# Breakout.net
KiCad netlist of a schematic drawn in EAGLE
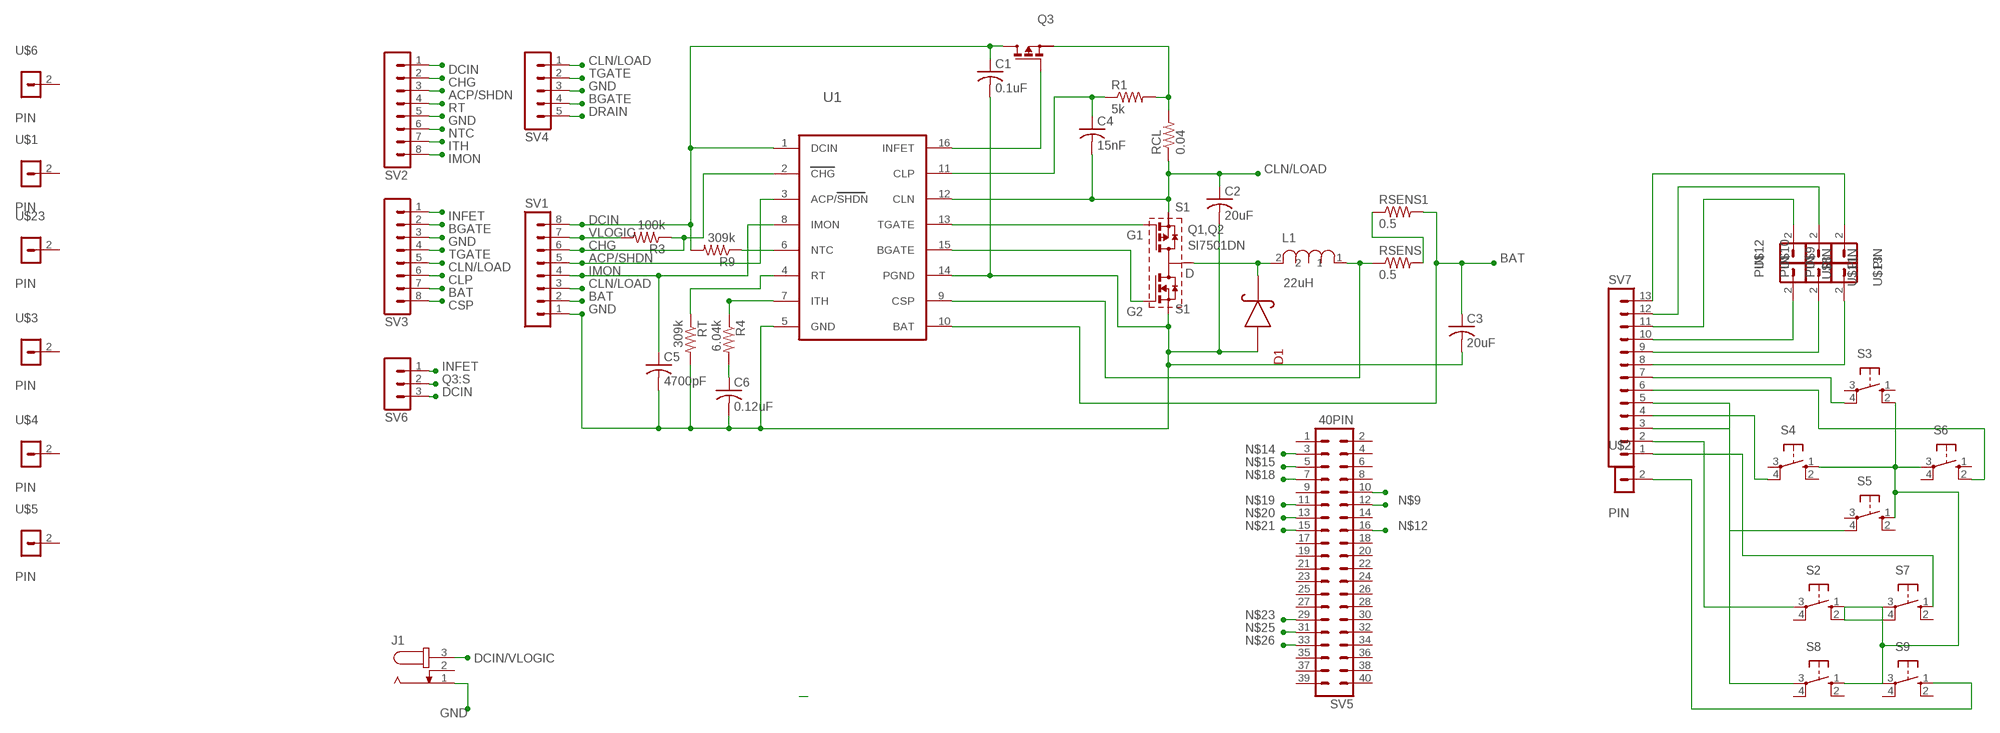
[diagram p0: schematic, sheet 1]

(export (version "E")
  (design (tool "Eeschema 10.0.6"))
  (components
    (comp (ref "C1")
      (value "0.1uF")
      (footprint "eagle-import:C1210")
      (libsource (lib "eagle-import") (part "C-USC1210"))
    )
    (comp (ref "C2")
      (value "20uF")
      (footprint "eagle-import:C1210")
      (libsource (lib "eagle-import") (part "C-USC1210"))
    )
    (comp (ref "C3")
      (value "20uF")
      (footprint "eagle-import:C1210")
      (libsource (lib "eagle-import") (part "C-USC1210"))
    )
    (comp (ref "C4")
      (value "15nF")
      (footprint "eagle-import:C1210")
      (libsource (lib "eagle-import") (part "C-USC1210"))
    )
    (comp (ref "C5")
      (value "4700pF")
      (footprint "eagle-import:C1210")
      (libsource (lib "eagle-import") (part "C-USC1210"))
    )
    (comp (ref "C6")
      (value "0.12uF")
      (footprint "eagle-import:C1210")
      (libsource (lib "eagle-import") (part "C-USC1210"))
    )
    (comp (ref "D1")
      (value "DIODE")
      (footprint "eagle-import:DIODE")
      (libsource (lib "eagle-import") (part "DIODE"))
    )
    (comp (ref "J1")
      (value "JACK-PLUG0")
      (footprint "eagle-import:SPC4077")
      (libsource (lib "eagle-import") (part "JACK-PLUG0"))
    )
    (comp (ref "L1")
      (value "22uH")
      (footprint "eagle-import:POWERINDUCTOR")
      (libsource (lib "eagle-import") (part "SDR1005INDUCTOR"))
    )
    (comp (ref "Q1,Q2")
      (value "SI7501DN")
      (footprint "eagle-import:POWERPAK")
      (libsource (lib "eagle-import") (part "SI7501DN"))
    )
    (comp (ref "Q3")
      (value "MOSFET")
      (footprint "eagle-import:SOT-23")
      (libsource (lib "eagle-import") (part "MOSFET"))
    )
    (comp (ref "R1")
      (value "5k")
      (footprint "eagle-import:R1206")
      (libsource (lib "eagle-import") (part "R-US_R1206"))
    )
    (comp (ref "R3")
      (value "100k")
      (footprint "eagle-import:R1206")
      (libsource (lib "eagle-import") (part "R-US_R1206"))
    )
    (comp (ref "R4")
      (value "6.04k")
      (footprint "eagle-import:R1206")
      (libsource (lib "eagle-import") (part "R-US_R1206"))
    )
    (comp (ref "R9")
      (value "309k")
      (footprint "eagle-import:R1206")
      (libsource (lib "eagle-import") (part "R-US_R1206"))
    )
    (comp (ref "RCL")
      (value "0.04")
      (footprint "eagle-import:R1206")
      (libsource (lib "eagle-import") (part "R-US_R1206"))
    )
    (comp (ref "RSENS")
      (value "0.5")
      (footprint "eagle-import:0612_1632")
      (libsource (lib "eagle-import") (part "0612/1632"))
    )
    (comp (ref "RSENS1")
      (value "0.5")
      (footprint "eagle-import:0612_1632")
      (libsource (lib "eagle-import") (part "0612/1632"))
    )
    (comp (ref "RT")
      (value "309k")
      (footprint "eagle-import:R1206")
      (libsource (lib "eagle-import") (part "R-US_R1206"))
    )
    (comp (ref "S2")
      (value "10-XX")
      (footprint "eagle-import:B3F-10XX")
      (fields (field (name "MPN") "B3F-1000"))
      (libsource (lib "eagle-import") (part "10-XX"))
    )
    (comp (ref "S3")
      (value "10-XX")
      (footprint "eagle-import:B3F-10XX")
      (fields (field (name "MPN") "B3F-1000"))
      (libsource (lib "eagle-import") (part "10-XX"))
    )
    (comp (ref "S4")
      (value "10-XX")
      (footprint "eagle-import:B3F-10XX")
      (fields (field (name "MPN") "B3F-1000"))
      (libsource (lib "eagle-import") (part "10-XX"))
    )
    (comp (ref "S5")
      (value "10-XX")
      (footprint "eagle-import:B3F-10XX")
      (fields (field (name "MPN") "B3F-1000"))
      (libsource (lib "eagle-import") (part "10-XX"))
    )
    (comp (ref "S6")
      (value "10-XX")
      (footprint "eagle-import:B3F-10XX")
      (fields (field (name "MPN") "B3F-1000"))
      (libsource (lib "eagle-import") (part "10-XX"))
    )
    (comp (ref "S7")
      (value "10-XX")
      (footprint "eagle-import:B3F-10XX")
      (fields (field (name "MPN") "B3F-1000"))
      (libsource (lib "eagle-import") (part "10-XX"))
    )
    (comp (ref "S8")
      (value "10-XX")
      (footprint "eagle-import:B3F-10XX")
      (fields (field (name "MPN") "B3F-1000"))
      (libsource (lib "eagle-import") (part "10-XX"))
    )
    (comp (ref "S9")
      (value "10-XX")
      (footprint "eagle-import:B3F-10XX")
      (fields (field (name "MPN") "B3F-1000"))
      (libsource (lib "eagle-import") (part "10-XX"))
    )
    (comp (ref "SV1")
      (value "MA08-1")
      (footprint "eagle-import:MA08-1")
      (libsource (lib "eagle-import") (part "MA08-1"))
    )
    (comp (ref "SV2")
      (value "MA08-1")
      (footprint "eagle-import:MA08-1")
      (libsource (lib "eagle-import") (part "MA08-1"))
    )
    (comp (ref "SV3")
      (value "MA08-1")
      (footprint "eagle-import:MA08-1")
      (libsource (lib "eagle-import") (part "MA08-1"))
    )
    (comp (ref "SV4")
      (value "MA05-1")
      (footprint "eagle-import:MA05-1")
      (libsource (lib "eagle-import") (part "MA05-1"))
    )
    (comp (ref "SV5")
      (value "40PIN")
      (footprint "eagle-import:40PINHEADDER")
      (libsource (lib "eagle-import") (part "40PIN"))
    )
    (comp (ref "SV6")
      (value "MA03-1")
      (footprint "eagle-import:MA03-1")
      (libsource (lib "eagle-import") (part "MA03-1"))
    )
    (comp (ref "SV7")
      (value "MA13-1")
      (footprint "eagle-import:MA13-1")
      (libsource (lib "eagle-import") (part "MA13-1"))
    )
    (comp (ref "U$1")
      (value "PIN")
      (footprint "eagle-import:PIN")
      (libsource (lib "eagle-import") (part "PIN"))
    )
    (comp (ref "U$2")
      (value "PIN")
      (footprint "eagle-import:PIN")
      (libsource (lib "eagle-import") (part "PIN"))
    )
    (comp (ref "U$3")
      (value "PIN")
      (footprint "eagle-import:PIN")
      (libsource (lib "eagle-import") (part "PIN"))
    )
    (comp (ref "U$4")
      (value "PIN")
      (footprint "eagle-import:PIN")
      (libsource (lib "eagle-import") (part "PIN"))
    )
    (comp (ref "U$5")
      (value "PIN")
      (footprint "eagle-import:PIN")
      (libsource (lib "eagle-import") (part "PIN"))
    )
    (comp (ref "U$6")
      (value "PIN")
      (footprint "eagle-import:PIN")
      (libsource (lib "eagle-import") (part "PIN"))
    )
    (comp (ref "U$8")
      (value "PIN")
      (footprint "eagle-import:PIN")
      (libsource (lib "eagle-import") (part "PIN"))
    )
    (comp (ref "U$9")
      (value "PIN")
      (footprint "eagle-import:PIN")
      (libsource (lib "eagle-import") (part "PIN"))
    )
    (comp (ref "U$10")
      (value "PIN")
      (footprint "eagle-import:PIN")
      (libsource (lib "eagle-import") (part "PIN"))
    )
    (comp (ref "U$11")
      (value "PIN")
      (footprint "eagle-import:PIN")
      (libsource (lib "eagle-import") (part "PIN"))
    )
    (comp (ref "U$12")
      (value "PIN")
      (footprint "eagle-import:PIN")
      (libsource (lib "eagle-import") (part "PIN"))
    )
    (comp (ref "U$13")
      (value "PIN")
      (footprint "eagle-import:PIN")
      (libsource (lib "eagle-import") (part "PIN"))
    )
    (comp (ref "U$23")
      (value "PIN")
      (footprint "eagle-import:PIN")
      (libsource (lib "eagle-import") (part "PIN"))
    )
    (comp (ref "U1")
      (value "LTC6004")
      (footprint "eagle-import:SSOP-16")
      (libsource (lib "eagle-import") (part "LTC6004"))
    )
  )
  (nets
    (net (code "1") (name "/ACP{slash}SHDN") (class "Default")
      (node (ref "SV1") (pin "5") (pinfunction "5_5") (pintype "passive"))
      (node (ref "SV2") (pin "3") (pinfunction "3_3") (pintype "passive"))
      (node (ref "U1") (pin "3") (pinfunction "ACP/SHDN_3") (pintype "power_in"))
    )
    (net (code "2") (name "/BAT") (class "Default")
      (node (ref "C3") (pin "1") (pinfunction "1_1") (pintype "passive"))
      (node (ref "RSENS1") (pin "2") (pinfunction "2_2") (pintype "passive"))
      (node (ref "SV1") (pin "2") (pinfunction "2_2") (pintype "passive"))
      (node (ref "SV3") (pin "7") (pinfunction "7_7") (pintype "passive"))
      (node (ref "U1") (pin "10") (pinfunction "BAT_10") (pintype "power_in"))
    )
    (net (code "3") (name "/BGATE") (class "Default")
      (node (ref "Q1,Q2") (pin "G2") (pinfunction "G2_G2") (pintype "passive"))
      (node (ref "SV3") (pin "2") (pinfunction "2_2") (pintype "passive"))
      (node (ref "SV4") (pin "4") (pinfunction "4_4") (pintype "passive"))
      (node (ref "U1") (pin "15") (pinfunction "BGATE_15") (pintype "power_in"))
    )
    (net (code "4") (name "/CHG") (class "Default")
      (node (ref "R3") (pin "1") (pinfunction "1_1") (pintype "passive"))
      (node (ref "SV1") (pin "6") (pinfunction "6_6") (pintype "passive"))
      (node (ref "SV2") (pin "2") (pinfunction "2_2") (pintype "passive"))
      (node (ref "U1") (pin "2") (pinfunction "CHG_2") (pintype "power_in"))
    )
    (net (code "5") (name "/CLN{slash}LOAD") (class "Default")
      (node (ref "C2") (pin "1") (pinfunction "1_1") (pintype "passive"))
      (node (ref "C4") (pin "2") (pinfunction "2_2") (pintype "passive"))
      (node (ref "Q1,Q2") (pin "S1") (pinfunction "S1_S1") (pintype "passive"))
      (node (ref "RCL") (pin "1") (pinfunction "1_1") (pintype "passive"))
      (node (ref "SV1") (pin "3") (pinfunction "3_3") (pintype "passive"))
      (node (ref "SV3") (pin "5") (pinfunction "5_5") (pintype "passive"))
      (node (ref "SV4") (pin "1") (pinfunction "1_1") (pintype "passive"))
      (node (ref "U1") (pin "12") (pinfunction "CLN_12") (pintype "power_in"))
    )
    (net (code "6") (name "/CLP") (class "Default")
      (node (ref "C4") (pin "1") (pinfunction "1_1") (pintype "passive"))
      (node (ref "R1") (pin "1") (pinfunction "1_1") (pintype "passive"))
      (node (ref "SV3") (pin "6") (pinfunction "6_6") (pintype "passive"))
      (node (ref "U1") (pin "11") (pinfunction "CLP_11") (pintype "output"))
    )
    (net (code "7") (name "/CSP") (class "Default")
      (node (ref "L1") (pin "1") (pinfunction "1_1") (pintype "passive"))
      (node (ref "RSENS") (pin "1") (pinfunction "1_1") (pintype "passive"))
      (node (ref "SV3") (pin "8") (pinfunction "8_8") (pintype "passive"))
      (node (ref "U1") (pin "9") (pinfunction "CSP_9") (pintype "power_in"))
    )
    (net (code "8") (name "/DCIN") (class "Default")
      (node (ref "C1") (pin "1") (pinfunction "1_1") (pintype "passive"))
      (node (ref "Q3") (pin "DRAIN") (pinfunction "D_DRAIN") (pintype "passive"))
      (node (ref "R9") (pin "2") (pinfunction "2_2") (pintype "passive"))
      (node (ref "SV1") (pin "8") (pinfunction "8_8") (pintype "passive"))
      (node (ref "SV2") (pin "1") (pinfunction "1_1") (pintype "passive"))
      (node (ref "SV6") (pin "3") (pinfunction "3_3") (pintype "passive"))
      (node (ref "U1") (pin "1") (pinfunction "DCIN_1") (pintype "power_in"))
    )
    (net (code "9") (name "/DCIN{slash}VLOGIC") (class "Default")
      (node (ref "J1") (pin "3") (pinfunction "3_3") (pintype "passive"))
    )
    (net (code "10") (name "/DRAIN") (class "Default")
      (node (ref "D1") (pin "P$1") (pinfunction "2_P$1") (pintype "bidirectional"))
      (node (ref "L1") (pin "2") (pinfunction "2_2") (pintype "passive"))
      (node (ref "Q1,Q2") (pin "D") (pinfunction "D_D") (pintype "passive"))
      (node (ref "SV4") (pin "5") (pinfunction "5_5") (pintype "passive"))
    )
    (net (code "11") (name "/GND") (class "Default")
      (node (ref "C1") (pin "2") (pinfunction "2_2") (pintype "passive"))
      (node (ref "C2") (pin "2") (pinfunction "2_2") (pintype "passive"))
      (node (ref "C3") (pin "2") (pinfunction "2_2") (pintype "passive"))
      (node (ref "C5") (pin "2") (pinfunction "2_2") (pintype "passive"))
      (node (ref "C6") (pin "2") (pinfunction "2_2") (pintype "passive"))
      (node (ref "D1") (pin "P$2") (pinfunction "1_P$2") (pintype "bidirectional"))
      (node (ref "J1") (pin "1") (pinfunction "1_1") (pintype "passive"))
      (node (ref "Q1,Q2") (pin "S2") (pinfunction "S2_S2") (pintype "passive"))
      (node (ref "RT") (pin "2") (pinfunction "2_2") (pintype "passive"))
      (node (ref "S2") (pin "1") (pinfunction "S_1") (pintype "passive"))
      (node (ref "S2") (pin "2") (pinfunction "S1_2") (pintype "passive"))
      (node (ref "S3") (pin "2") (pinfunction "S1_2") (pintype "passive"))
      (node (ref "S4") (pin "1") (pinfunction "S_1") (pintype "passive"))
      (node (ref "S5") (pin "1") (pinfunction "S_1") (pintype "passive"))
      (node (ref "S6") (pin "3") (pinfunction "P_3") (pintype "passive"))
      (node (ref "S7") (pin "3") (pinfunction "P_3") (pintype "passive"))
      (node (ref "S7") (pin "4") (pinfunction "P1_4") (pintype "passive"))
      (node (ref "S8") (pin "1") (pinfunction "S_1") (pintype "passive"))
      (node (ref "S9") (pin "3") (pinfunction "P_3") (pintype "passive"))
      (node (ref "SV1") (pin "1") (pinfunction "1_1") (pintype "passive"))
      (node (ref "SV2") (pin "5") (pinfunction "5_5") (pintype "passive"))
      (node (ref "SV3") (pin "3") (pinfunction "3_3") (pintype "passive"))
      (node (ref "SV4") (pin "3") (pinfunction "3_3") (pintype "passive"))
      (node (ref "U1") (pin "14") (pinfunction "PGND_14") (pintype "power_in"))
      (node (ref "U1") (pin "5") (pinfunction "GND_5") (pintype "input"))
    )
    (net (code "12") (name "/IMON") (class "Default")
      (node (ref "C5") (pin "1") (pinfunction "1_1") (pintype "passive"))
      (node (ref "SV1") (pin "4") (pinfunction "4_4") (pintype "passive"))
      (node (ref "SV2") (pin "8") (pinfunction "8_8") (pintype "passive"))
      (node (ref "U1") (pin "8") (pinfunction "IMON_8") (pintype "power_in"))
    )
    (net (code "13") (name "/INFET") (class "Default")
      (node (ref "Q3") (pin "GATE") (pinfunction "G_GATE") (pintype "passive"))
      (node (ref "SV3") (pin "1") (pinfunction "1_1") (pintype "passive"))
      (node (ref "SV6") (pin "1") (pinfunction "1_1") (pintype "passive"))
      (node (ref "U1") (pin "16") (pinfunction "INFET_16") (pintype "output"))
    )
    (net (code "14") (name "/ITH") (class "Default")
      (node (ref "R4") (pin "1") (pinfunction "1_1") (pintype "passive"))
      (node (ref "SV2") (pin "7") (pinfunction "7_7") (pintype "passive"))
      (node (ref "U1") (pin "7") (pinfunction "ITH_7") (pintype "input"))
    )
    (net (code "15") (name "/N$9") (class "Default")
      (node (ref "SV5") (pin "12") (pinfunction "12_12") (pintype "passive"))
    )
    (net (code "16") (name "/N$12") (class "Default")
      (node (ref "SV5") (pin "16") (pinfunction "16_16") (pintype "passive"))
    )
    (net (code "17") (name "/N$14") (class "Default")
      (node (ref "SV5") (pin "3") (pinfunction "3_3") (pintype "passive"))
    )
    (net (code "18") (name "/N$15") (class "Default")
      (node (ref "SV5") (pin "5") (pinfunction "5_5") (pintype "passive"))
    )
    (net (code "19") (name "/N$18") (class "Default")
      (node (ref "SV5") (pin "7") (pinfunction "7_7") (pintype "passive"))
    )
    (net (code "20") (name "/N$19") (class "Default")
      (node (ref "SV5") (pin "11") (pinfunction "11_11") (pintype "passive"))
    )
    (net (code "21") (name "/N$20") (class "Default")
      (node (ref "SV5") (pin "13") (pinfunction "13_13") (pintype "passive"))
    )
    (net (code "22") (name "/N$21") (class "Default")
      (node (ref "SV5") (pin "15") (pinfunction "15_15") (pintype "passive"))
    )
    (net (code "23") (name "/N$23") (class "Default")
      (node (ref "SV5") (pin "29") (pinfunction "29_29") (pintype "passive"))
    )
    (net (code "24") (name "/N$25") (class "Default")
      (node (ref "SV5") (pin "31") (pinfunction "31_31") (pintype "passive"))
    )
    (net (code "25") (name "/N$26") (class "Default")
      (node (ref "SV5") (pin "33") (pinfunction "33_33") (pintype "passive"))
    )
    (net (code "26") (name "/NTC") (class "Default")
      (node (ref "R9") (pin "1") (pinfunction "1_1") (pintype "passive"))
      (node (ref "SV2") (pin "6") (pinfunction "6_6") (pintype "passive"))
      (node (ref "U1") (pin "6") (pinfunction "NTC_6") (pintype "power_in"))
    )
    (net (code "27") (name "/Q3:S") (class "Default")
      (node (ref "Q3") (pin "SOURCE") (pinfunction "S_SOURCE") (pintype "passive"))
      (node (ref "R1") (pin "2") (pinfunction "2_2") (pintype "passive"))
      (node (ref "RCL") (pin "2") (pinfunction "2_2") (pintype "passive"))
      (node (ref "SV6") (pin "2") (pinfunction "2_2") (pintype "passive"))
    )
    (net (code "28") (name "/RT") (class "Default")
      (node (ref "RT") (pin "1") (pinfunction "1_1") (pintype "passive"))
      (node (ref "SV2") (pin "4") (pinfunction "4_4") (pintype "passive"))
      (node (ref "U1") (pin "4") (pinfunction "RT_4") (pintype "input"))
    )
    (net (code "29") (name "/TGATE") (class "Default")
      (node (ref "Q1,Q2") (pin "G1") (pinfunction "G1_G1") (pintype "passive"))
      (node (ref "SV3") (pin "4") (pinfunction "4_4") (pintype "passive"))
      (node (ref "SV4") (pin "2") (pinfunction "2_2") (pintype "passive"))
      (node (ref "U1") (pin "13") (pinfunction "TGATE_13") (pintype "input"))
    )
    (net (code "30") (name "/VLOGIC") (class "Default")
      (node (ref "R3") (pin "2") (pinfunction "2_2") (pintype "passive"))
      (node (ref "SV1") (pin "7") (pinfunction "7_7") (pintype "passive"))
    )
    (net (code "31") (name "Net-(C6-Pad1)") (class "Default")
      (node (ref "C6") (pin "1") (pinfunction "1_1") (pintype "passive"))
      (node (ref "R4") (pin "2") (pinfunction "2_2") (pintype "passive"))
    )
    (net (code "32") (name "Net-(RSENS-Pad2)") (class "Default")
      (node (ref "RSENS") (pin "2") (pinfunction "2_2") (pintype "passive"))
      (node (ref "RSENS1") (pin "1") (pinfunction "1_1") (pintype "passive"))
    )
    (net (code "33") (name "Net-(S2-P)") (class "Default")
      (node (ref "S2") (pin "3") (pinfunction "P_3") (pintype "passive"))
      (node (ref "SV7") (pin "2") (pinfunction "2_2") (pintype "passive"))
    )
    (net (code "34") (name "Net-(S3-P1)") (class "Default")
      (node (ref "S3") (pin "4") (pinfunction "P1_4") (pintype "passive"))
      (node (ref "SV7") (pin "7") (pinfunction "7_7") (pintype "passive"))
    )
    (net (code "35") (name "Net-(S4-P1)") (class "Default")
      (node (ref "S4") (pin "4") (pinfunction "P1_4") (pintype "passive"))
      (node (ref "SV7") (pin "4") (pinfunction "4_4") (pintype "passive"))
    )
    (net (code "36") (name "Net-(S5-P1)") (class "Default")
      (node (ref "S5") (pin "4") (pinfunction "P1_4") (pintype "passive"))
      (node (ref "SV7") (pin "5") (pinfunction "5_5") (pintype "passive"))
    )
    (net (code "37") (name "Net-(S6-S1)") (class "Default")
      (node (ref "S6") (pin "2") (pinfunction "S1_2") (pintype "passive"))
      (node (ref "SV7") (pin "6") (pinfunction "6_6") (pintype "passive"))
    )
    (net (code "38") (name "Net-(S7-S)") (class "Default")
      (node (ref "S7") (pin "1") (pinfunction "S_1") (pintype "passive"))
      (node (ref "SV7") (pin "1") (pinfunction "1_1") (pintype "passive"))
    )
    (net (code "39") (name "Net-(S8-P)") (class "Default")
      (node (ref "S8") (pin "3") (pinfunction "P_3") (pintype "passive"))
      (node (ref "SV7") (pin "3") (pinfunction "3_3") (pintype "passive"))
    )
    (net (code "40") (name "Net-(S9-S)") (class "Default")
      (node (ref "S9") (pin "1") (pinfunction "S_1") (pintype "passive"))
      (node (ref "U$2") (pin "2") (pinfunction "2_2") (pintype "passive"))
    )
    (net (code "41") (name "Net-(SV7-Pad8)") (class "Default")
      (node (ref "SV7") (pin "8") (pinfunction "8_8") (pintype "passive"))
      (node (ref "U$13") (pin "2") (pinfunction "2_2") (pintype "passive"))
    )
    (net (code "42") (name "Net-(SV7-Pad9)") (class "Default")
      (node (ref "SV7") (pin "9") (pinfunction "9_9") (pintype "passive"))
      (node (ref "U$11") (pin "2") (pinfunction "2_2") (pintype "passive"))
    )
    (net (code "43") (name "Net-(SV7-Pad10)") (class "Default")
      (node (ref "SV7") (pin "10") (pinfunction "10_10") (pintype "passive"))
      (node (ref "U$8") (pin "2") (pinfunction "2_2") (pintype "passive"))
    )
    (net (code "44") (name "Net-(SV7-Pad11)") (class "Default")
      (node (ref "SV7") (pin "11") (pinfunction "11_11") (pintype "passive"))
      (node (ref "U$12") (pin "2") (pinfunction "2_2") (pintype "passive"))
    )
    (net (code "45") (name "Net-(SV7-Pad12)") (class "Default")
      (node (ref "SV7") (pin "12") (pinfunction "12_12") (pintype "passive"))
      (node (ref "U$10") (pin "2") (pinfunction "2_2") (pintype "passive"))
    )
    (net (code "46") (name "Net-(SV7-Pad13)") (class "Default")
      (node (ref "SV7") (pin "13") (pinfunction "13_13") (pintype "passive"))
      (node (ref "U$9") (pin "2") (pinfunction "2_2") (pintype "passive"))
    )
    (net (code "47") (name "unconnected-(J1-Pad2)") (class "Default")
      (node (ref "J1") (pin "2") (pinfunction "2_2") (pintype "passive"))
    )
    (net (code "48") (name "unconnected-(S2-P1-Pad4)") (class "Default")
      (node (ref "S2") (pin "4") (pinfunction "P1_4") (pintype "passive"))
    )
    (net (code "49") (name "unconnected-(S3-P-Pad3)") (class "Default")
      (node (ref "S3") (pin "3") (pinfunction "P_3") (pintype "passive"))
    )
    (net (code "50") (name "unconnected-(S3-S-Pad1)") (class "Default")
      (node (ref "S3") (pin "1") (pinfunction "S_1") (pintype "passive"))
    )
    (net (code "51") (name "unconnected-(S4-P-Pad3)") (class "Default")
      (node (ref "S4") (pin "3") (pinfunction "P_3") (pintype "passive"))
    )
    (net (code "52") (name "unconnected-(S4-S1-Pad2)") (class "Default")
      (node (ref "S4") (pin "2") (pinfunction "S1_2") (pintype "passive"))
    )
    (net (code "53") (name "unconnected-(S5-P-Pad3)") (class "Default")
      (node (ref "S5") (pin "3") (pinfunction "P_3") (pintype "passive"))
    )
    (net (code "54") (name "unconnected-(S5-S1-Pad2)") (class "Default")
      (node (ref "S5") (pin "2") (pinfunction "S1_2") (pintype "passive"))
    )
    (net (code "55") (name "unconnected-(S6-P1-Pad4)") (class "Default")
      (node (ref "S6") (pin "4") (pinfunction "P1_4") (pintype "passive"))
    )
    (net (code "56") (name "unconnected-(S6-S-Pad1)") (class "Default")
      (node (ref "S6") (pin "1") (pinfunction "S_1") (pintype "passive"))
    )
    (net (code "57") (name "unconnected-(S7-S1-Pad2)") (class "Default")
      (node (ref "S7") (pin "2") (pinfunction "S1_2") (pintype "passive"))
    )
    (net (code "58") (name "unconnected-(S8-P1-Pad4)") (class "Default")
      (node (ref "S8") (pin "4") (pinfunction "P1_4") (pintype "passive"))
    )
    (net (code "59") (name "unconnected-(S8-S1-Pad2)") (class "Default")
      (node (ref "S8") (pin "2") (pinfunction "S1_2") (pintype "passive"))
    )
    (net (code "60") (name "unconnected-(S9-P1-Pad4)") (class "Default")
      (node (ref "S9") (pin "4") (pinfunction "P1_4") (pintype "passive"))
    )
    (net (code "61") (name "unconnected-(S9-S1-Pad2)") (class "Default")
      (node (ref "S9") (pin "2") (pinfunction "S1_2") (pintype "passive"))
    )
    (net (code "62") (name "unconnected-(SV5-Pad1)") (class "Default")
      (node (ref "SV5") (pin "1") (pinfunction "1_1") (pintype "passive"))
    )
    (net (code "63") (name "unconnected-(SV5-Pad2)") (class "Default")
      (node (ref "SV5") (pin "2") (pinfunction "2_2") (pintype "passive"))
    )
    (net (code "64") (name "unconnected-(SV5-Pad4)") (class "Default")
      (node (ref "SV5") (pin "4") (pinfunction "4_4") (pintype "passive"))
    )
    (net (code "65") (name "unconnected-(SV5-Pad6)") (class "Default")
      (node (ref "SV5") (pin "6") (pinfunction "6_6") (pintype "passive"))
    )
    (net (code "66") (name "unconnected-(SV5-Pad8)") (class "Default")
      (node (ref "SV5") (pin "8") (pinfunction "8_8") (pintype "passive"))
    )
    (net (code "67") (name "unconnected-(SV5-Pad9)") (class "Default")
      (node (ref "SV5") (pin "9") (pinfunction "9_9") (pintype "passive"))
    )
    (net (code "68") (name "unconnected-(SV5-Pad10)") (class "Default")
      (node (ref "SV5") (pin "10") (pinfunction "10_10") (pintype "passive"))
    )
    (net (code "69") (name "unconnected-(SV5-Pad14)") (class "Default")
      (node (ref "SV5") (pin "14") (pinfunction "14_14") (pintype "passive"))
    )
    (net (code "70") (name "unconnected-(SV5-Pad17)") (class "Default")
      (node (ref "SV5") (pin "17") (pinfunction "17_17") (pintype "passive"))
    )
    (net (code "71") (name "unconnected-(SV5-Pad18)") (class "Default")
      (node (ref "SV5") (pin "18") (pinfunction "18_18") (pintype "passive"))
    )
    (net (code "72") (name "unconnected-(SV5-Pad19)") (class "Default")
      (node (ref "SV5") (pin "19") (pinfunction "19_19") (pintype "passive"))
    )
    (net (code "73") (name "unconnected-(SV5-Pad20)") (class "Default")
      (node (ref "SV5") (pin "20") (pinfunction "20_20") (pintype "passive"))
    )
    (net (code "74") (name "unconnected-(SV5-Pad21)") (class "Default")
      (node (ref "SV5") (pin "21") (pinfunction "21_21") (pintype "passive"))
    )
    (net (code "75") (name "unconnected-(SV5-Pad22)") (class "Default")
      (node (ref "SV5") (pin "22") (pinfunction "22_22") (pintype "passive"))
    )
    (net (code "76") (name "unconnected-(SV5-Pad23)") (class "Default")
      (node (ref "SV5") (pin "23") (pinfunction "23_23") (pintype "passive"))
    )
    (net (code "77") (name "unconnected-(SV5-Pad24)") (class "Default")
      (node (ref "SV5") (pin "24") (pinfunction "24_24") (pintype "passive"))
    )
    (net (code "78") (name "unconnected-(SV5-Pad25)") (class "Default")
      (node (ref "SV5") (pin "25") (pinfunction "25_25") (pintype "passive"))
    )
    (net (code "79") (name "unconnected-(SV5-Pad26)") (class "Default")
      (node (ref "SV5") (pin "26") (pinfunction "26_26") (pintype "passive"))
    )
    (net (code "80") (name "unconnected-(SV5-Pad27)") (class "Default")
      (node (ref "SV5") (pin "27") (pinfunction "27_27") (pintype "passive"))
    )
    (net (code "81") (name "unconnected-(SV5-Pad28)") (class "Default")
      (node (ref "SV5") (pin "28") (pinfunction "28_28") (pintype "passive"))
    )
    (net (code "82") (name "unconnected-(SV5-Pad30)") (class "Default")
      (node (ref "SV5") (pin "30") (pinfunction "30_30") (pintype "passive"))
    )
    (net (code "83") (name "unconnected-(SV5-Pad32)") (class "Default")
      (node (ref "SV5") (pin "32") (pinfunction "32_32") (pintype "passive"))
    )
    (net (code "84") (name "unconnected-(SV5-Pad34)") (class "Default")
      (node (ref "SV5") (pin "34") (pinfunction "34_34") (pintype "passive"))
    )
    (net (code "85") (name "unconnected-(SV5-Pad35)") (class "Default")
      (node (ref "SV5") (pin "35") (pinfunction "35_35") (pintype "passive"))
    )
    (net (code "86") (name "unconnected-(SV5-Pad36)") (class "Default")
      (node (ref "SV5") (pin "36") (pinfunction "36_36") (pintype "passive"))
    )
    (net (code "87") (name "unconnected-(SV5-Pad37)") (class "Default")
      (node (ref "SV5") (pin "37") (pinfunction "37_37") (pintype "passive"))
    )
    (net (code "88") (name "unconnected-(SV5-Pad38)") (class "Default")
      (node (ref "SV5") (pin "38") (pinfunction "38_38") (pintype "passive"))
    )
    (net (code "89") (name "unconnected-(SV5-Pad39)") (class "Default")
      (node (ref "SV5") (pin "39") (pinfunction "39_39") (pintype "passive"))
    )
    (net (code "90") (name "unconnected-(SV5-Pad40)") (class "Default")
      (node (ref "SV5") (pin "40") (pinfunction "40_40") (pintype "passive"))
    )
    (net (code "91") (name "unconnected-(U$1-Pad2)") (class "Default")
      (node (ref "U$1") (pin "2") (pinfunction "2_2") (pintype "passive"))
    )
    (net (code "92") (name "unconnected-(U$3-Pad2)") (class "Default")
      (node (ref "U$3") (pin "2") (pinfunction "2_2") (pintype "passive"))
    )
    (net (code "93") (name "unconnected-(U$4-Pad2)") (class "Default")
      (node (ref "U$4") (pin "2") (pinfunction "2_2") (pintype "passive"))
    )
    (net (code "94") (name "unconnected-(U$5-Pad2)") (class "Default")
      (node (ref "U$5") (pin "2") (pinfunction "2_2") (pintype "passive"))
    )
    (net (code "95") (name "unconnected-(U$6-Pad2)") (class "Default")
      (node (ref "U$6") (pin "2") (pinfunction "2_2") (pintype "passive"))
    )
    (net (code "96") (name "unconnected-(U$23-Pad2)") (class "Default")
      (node (ref "U$23") (pin "2") (pinfunction "2_2") (pintype "passive"))
    )
  )
)
